# Power.net
KiCad netlist of a schematic drawn in Altium Designer
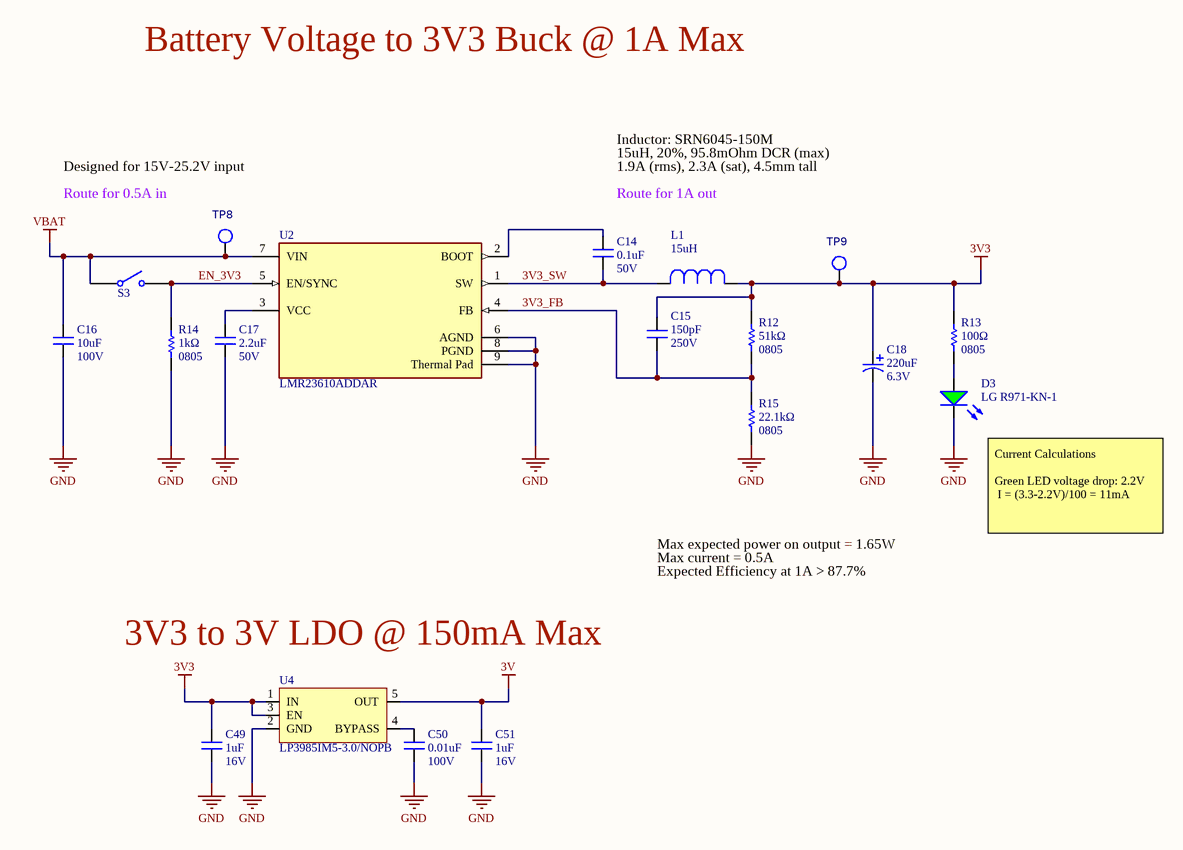
[diagram p0: Power.SchDoc]

(export (version "E")
  (design (tool "Eeschema 10.0.6"))
  (components
    (comp (ref "C14")
      (value "0.1uF")
      (footprint "CAPC2012X140N")
      (description "CAP CER 0.1UF 50V X7R 0805")
      (fields
        (field (name "TOLERANCE") "10%")
        (field (name "VOLTAGE RATING") "50V")
        (field (name "Comment") "CAP_0.1uF_50V_0805")
      )
      (libsource (lib "UWRT_Schematic_Library_2020") (part "CAP_0.1uF_50V_0805"))
    )
    (comp (ref "C15")
      (value "150pF")
      (footprint "CAPC2012X140N")
      (description "CAP CER 150PF 250V C0G/NP0 0805")
      (fields
        (field (name "TOLERANCE") "5%")
        (field (name "VOLTAGE RATING") "250V")
        (field (name "Comment") "CAP_150pF_250V_0805")
      )
      (libsource (lib "UWRT_Schematic_Library_2020") (part "CAP_150pF_250V_0805"))
    )
    (comp (ref "C16")
      (value "10uF")
      (footprint "CAPC1210(3225)")
      (description "CAP CER 10UF 100V X7S 1210")
      (fields (field (name "VOLTAGE RATING") "100V") (field (name "Comment") "CAP_10uF_100V_1210"))
      (libsource (lib "UWRT_Schematic_Library_2020") (part "CAP_10uF_100V_1210"))
    )
    (comp (ref "C17")
      (value "2.2uF")
      (footprint "CAPC1206(3216)")
      (description "CAP CER 2.2UF 50V X7R 1206")
      (fields
        (field (name "TOLERANCE") "10%")
        (field (name "VOLTAGE") "50V")
        (field (name "VOLTAGE RATING") "50V")
      )
      (libsource (lib "UWRT_Schematic_Library_2020") (part "CAP_2.2uF_50V_1206"))
    )
    (comp (ref "C18")
      (value "220uF")
      (footprint "PCAP_SVP_B6_PA00")
      (description "CAP ALUM POLY 220UF 20% 6.3V SMD")
      (fields (field (name "VOLTAGE RATING") "6.3V") (field (name "Comment") "CAP_220uF_6.3V_SMD"))
      (libsource (lib "UWRT_Schematic_Library_2020") (part "CAP_220uF_6.3V_SMD"))
    )
    (comp (ref "C49")
      (value "1uF")
      (footprint "CAPC2012X140N")
      (description "CAP CER 1UF 16V X7R 0805")
      (fields
        (field (name "TOLERANCE") "10%")
        (field (name "VOLTAGE RATING") "16V")
        (field (name "Comment") "CAP_1uF_16V_0805")
      )
      (libsource (lib "UWRT_Schematic_Library_2020") (part "CAP_1uF_16V_0805"))
    )
    (comp (ref "C50")
      (value "0.01uF")
      (footprint "CAPC2012X140N")
      (description "CAP CER 10000PF 100V X7R 0805")
      (fields
        (field (name "TOLERANCE") "10%")
        (field (name "VOLTAGE RATING") "100V")
        (field (name "Comment") "CAP_0.01uF_100V_0805")
      )
      (libsource (lib "UWRT_Schematic_Library_2020") (part "CAP_0.01uF_100V_0805"))
    )
    (comp (ref "C51")
      (value "1uF")
      (footprint "CAPC2012X140N")
      (description "CAP CER 1UF 16V X7R 0805")
      (fields
        (field (name "TOLERANCE") "10%")
        (field (name "VOLTAGE RATING") "16V")
        (field (name "Comment") "CAP_1uF_16V_0805")
      )
      (libsource (lib "UWRT_Schematic_Library_2020") (part "CAP_1uF_16V_0805"))
    )
    (comp (ref "D3")
      (value "DIO_LED_G")
      (footprint "LED_0805_LINE")
      (description "LED GREEN DIFFUSED 0805 SMD")
      (fields (field (name "MANUFACTURER PART NUMBER 1") "LG R971-KN-1"))
      (libsource (lib "UWRT_Schematic_Library_2020") (part "DIO_LED_G"))
    )
    (comp (ref "L1")
      (value "SRN6045-150M")
      (footprint "IND_BOURNS_SRN6045")
      (description "FIXED IND 15UH 1.9A 95.8MOHM SMD")
      (fields (field (name "TOLERANCE") "20%") (field (name "INDUCTANCE") "15uH"))
      (libsource (lib "UWRT_Schematic_Library_2020") (part "IND_15uH_1.9A"))
    )
    (comp (ref "R12")
      (value "51kΩ")
      (footprint "RESC2012X60N")
      (description "RES SMD 51K OHM 1% 1/8W 0805")
      (fields
        (field (name "CASE CODE (IMPERIAL)") "0805")
        (field (name "TOLERANCE") "1%")
        (field (name "Comment") "RES_51kΩ_0805")
      )
      (libsource (lib "UWRT_Schematic_Library_2020") (part "RES_51kΩ_0805"))
    )
    (comp (ref "R13")
      (value "100Ω")
      (footprint "RESC2012X60N")
      (description "RES SMD 100 OHM 1% 1/8W 0805")
      (fields (field (name "CASE CODE (IMPERIAL)") "0805") (field (name "Comment") "RES_100Ω_0805"))
      (libsource (lib "UWRT_Schematic_Library_2020") (part "RES_100Ω_0805"))
    )
    (comp (ref "R14")
      (value "1kΩ")
      (footprint "RESC2012X60N")
      (description "RES SMD 1K OHM 1% 1/8W 0805")
      (fields
        (field (name "CASE CODE (IMPERIAL)") "0805")
        (field (name "TOLERANCE") "1%")
        (field (name "Comment") "RES_1kΩ_0805")
      )
      (libsource (lib "UWRT_Schematic_Library_2020") (part "RES_1kΩ_0805"))
    )
    (comp (ref "R15")
      (value "RES_22.1kΩ_0805")
      (footprint "RESC2012X60N")
      (description "RES SMD 22.1K OHM 1% 1/8W 0805")
      (fields
        (field (name "CASE CODE (IMPERIAL)") "0805")
        (field (name "RESISTANCE") "22.1kΩ")
        (field (name "TOLERANCE") "1%")
      )
      (libsource (lib "UWRT_Schematic_Library_2020") (part "RES_22.1kΩ_0805"))
    )
    (comp (ref "S3")
      (value "GF-123-0054")
      (footprint "GF1230054")
      (description "SWITCH SLIDE SPST 500mA (DC) 8.5A (AC) 125V")
      (libsource (lib "UWRT_Schematic_Library_2020") (part "GF-123-0054"))
    )
    (comp (ref "TP8")
      (value "TESTPOINT_LOOP")
      (footprint "TESTPOINT_LOOP")
      (description "Loop testpoint through-hole pad")
      (libsource (lib "UWRT_Schematic_Library_2020") (part "TESTPOINT_LOOP"))
    )
    (comp (ref "TP9")
      (value "TESTPOINT_LOOP")
      (footprint "TESTPOINT_LOOP")
      (description "Loop testpoint through-hole pad")
      (libsource (lib "UWRT_Schematic_Library_2020") (part "TESTPOINT_LOOP"))
    )
    (comp (ref "U2")
      (value "LMR23610ADDAR")
      (footprint "8-SO PowerPad")
      (description "IC REG BUCK ADJUSTABLE 1A 8SOPWR")
      (fields (field (name "OCTOPART") "https://octopart.com/lmr23610addar-texas+instruments-68058948"))
      (libsource (lib "UWRT_Schematic_Library_2020") (part "BUCK_1-28VOUT_1A"))
    )
    (comp (ref "U4")
      (value "LP3985IM5-3.0/NOPB")
      (footprint "SOT23-5")
      (description "IC REG LINEAR 3V 150MA SOT23-5")
      (libsource (lib "UWRT_Schematic_Library_2020") (part "LP3985IM5-3.0/NOPB"))
    )
  )
  (nets
    (net (code "1") (name "/3V3_FB") (class "Default")
      (node (ref "C15") (pin "2") (pinfunction "2_2") (pintype "passive"))
      (node (ref "R12") (pin "1") (pinfunction "1_1") (pintype "passive"))
      (node (ref "R15") (pin "2") (pinfunction "2_2") (pintype "passive"))
      (node (ref "U2") (pin "4") (pinfunction "FB_4") (pintype "input"))
    )
    (net (code "2") (name "/3V3_SW") (class "Default")
      (node (ref "C14") (pin "1") (pinfunction "1_1") (pintype "passive"))
      (node (ref "L1") (pin "2") (pinfunction "2_2") (pintype "passive"))
      (node (ref "U2") (pin "1") (pinfunction "SW_1") (pintype "output"))
    )
    (net (code "3") (name "/EN_3V3") (class "Default")
      (node (ref "R14") (pin "2") (pinfunction "2_2") (pintype "passive"))
      (node (ref "S3") (pin "2") (pintype "passive"))
      (node (ref "U2") (pin "5") (pinfunction "EN/SYNC_5") (pintype "input"))
    )
    (net (code "4") (name "3V") (class "Default")
      (node (ref "C51") (pin "2") (pinfunction "2_2") (pintype "passive"))
      (node (ref "U4") (pin "5") (pinfunction "OUT_5") (pintype "passive"))
    )
    (net (code "5") (name "3V3") (class "Default")
      (node (ref "C15") (pin "1") (pinfunction "1_1") (pintype "passive"))
      (node (ref "C18") (pin "1") (pinfunction "1_1") (pintype "passive"))
      (node (ref "C49") (pin "2") (pinfunction "2_2") (pintype "passive"))
      (node (ref "L1") (pin "1") (pinfunction "1_1") (pintype "passive"))
      (node (ref "R12") (pin "2") (pinfunction "2_2") (pintype "passive"))
      (node (ref "R13") (pin "2") (pinfunction "2_2") (pintype "passive"))
      (node (ref "TP9") (pin "1") (pintype "passive"))
      (node (ref "U4") (pin "1") (pinfunction "IN_1") (pintype "passive"))
      (node (ref "U4") (pin "3") (pinfunction "EN_3") (pintype "passive"))
    )
    (net (code "6") (name "GND") (class "Default")
      (node (ref "C16") (pin "1") (pinfunction "1_1") (pintype "passive"))
      (node (ref "C17") (pin "1") (pinfunction "1_1") (pintype "passive"))
      (node (ref "C18") (pin "2") (pinfunction "2_2") (pintype "passive"))
      (node (ref "C49") (pin "1") (pinfunction "1_1") (pintype "passive"))
      (node (ref "C50") (pin "1") (pinfunction "1_1") (pintype "passive"))
      (node (ref "C51") (pin "1") (pinfunction "1_1") (pintype "passive"))
      (node (ref "D3") (pin "2") (pinfunction "K_2") (pintype "passive"))
      (node (ref "R14") (pin "1") (pinfunction "1_1") (pintype "passive"))
      (node (ref "R15") (pin "1") (pinfunction "1_1") (pintype "passive"))
      (node (ref "U2") (pin "6") (pinfunction "AGND_6") (pintype "power_in"))
      (node (ref "U2") (pin "8") (pinfunction "PGND_8") (pintype "power_in"))
      (node (ref "U2") (pin "9") (pinfunction "Thermal_Pad_9") (pintype "power_in"))
      (node (ref "U4") (pin "2") (pinfunction "GND_2") (pintype "passive"))
    )
    (net (code "7") (name "Net-(D3-A)") (class "Default")
      (node (ref "D3") (pin "1") (pinfunction "A_1") (pintype "passive"))
      (node (ref "R13") (pin "1") (pinfunction "1_1") (pintype "passive"))
    )
    (net (code "8") (name "Net-(U2-BOOT)") (class "Default")
      (node (ref "C14") (pin "2") (pinfunction "2_2") (pintype "passive"))
      (node (ref "U2") (pin "2") (pinfunction "BOOT_2") (pintype "output"))
    )
    (net (code "9") (name "Net-(U2-VCC)") (class "Default")
      (node (ref "C17") (pin "2") (pinfunction "2_2") (pintype "passive"))
      (node (ref "U2") (pin "3") (pinfunction "VCC_3") (pintype "power_in"))
    )
    (net (code "10") (name "Net-(U4-BYPASS)") (class "Default")
      (node (ref "C50") (pin "2") (pinfunction "2_2") (pintype "passive"))
      (node (ref "U4") (pin "4") (pinfunction "BYPASS_4") (pintype "passive"))
    )
    (net (code "11") (name "VBAT") (class "Default")
      (node (ref "C16") (pin "2") (pinfunction "2_2") (pintype "passive"))
      (node (ref "S3") (pin "1") (pintype "passive"))
      (node (ref "TP8") (pin "1") (pintype "passive"))
      (node (ref "U2") (pin "7") (pinfunction "VIN_7") (pintype "power_in"))
    )
  )
)
